# dat1.net
KiCad netlist of a schematic drawn in EAGLE
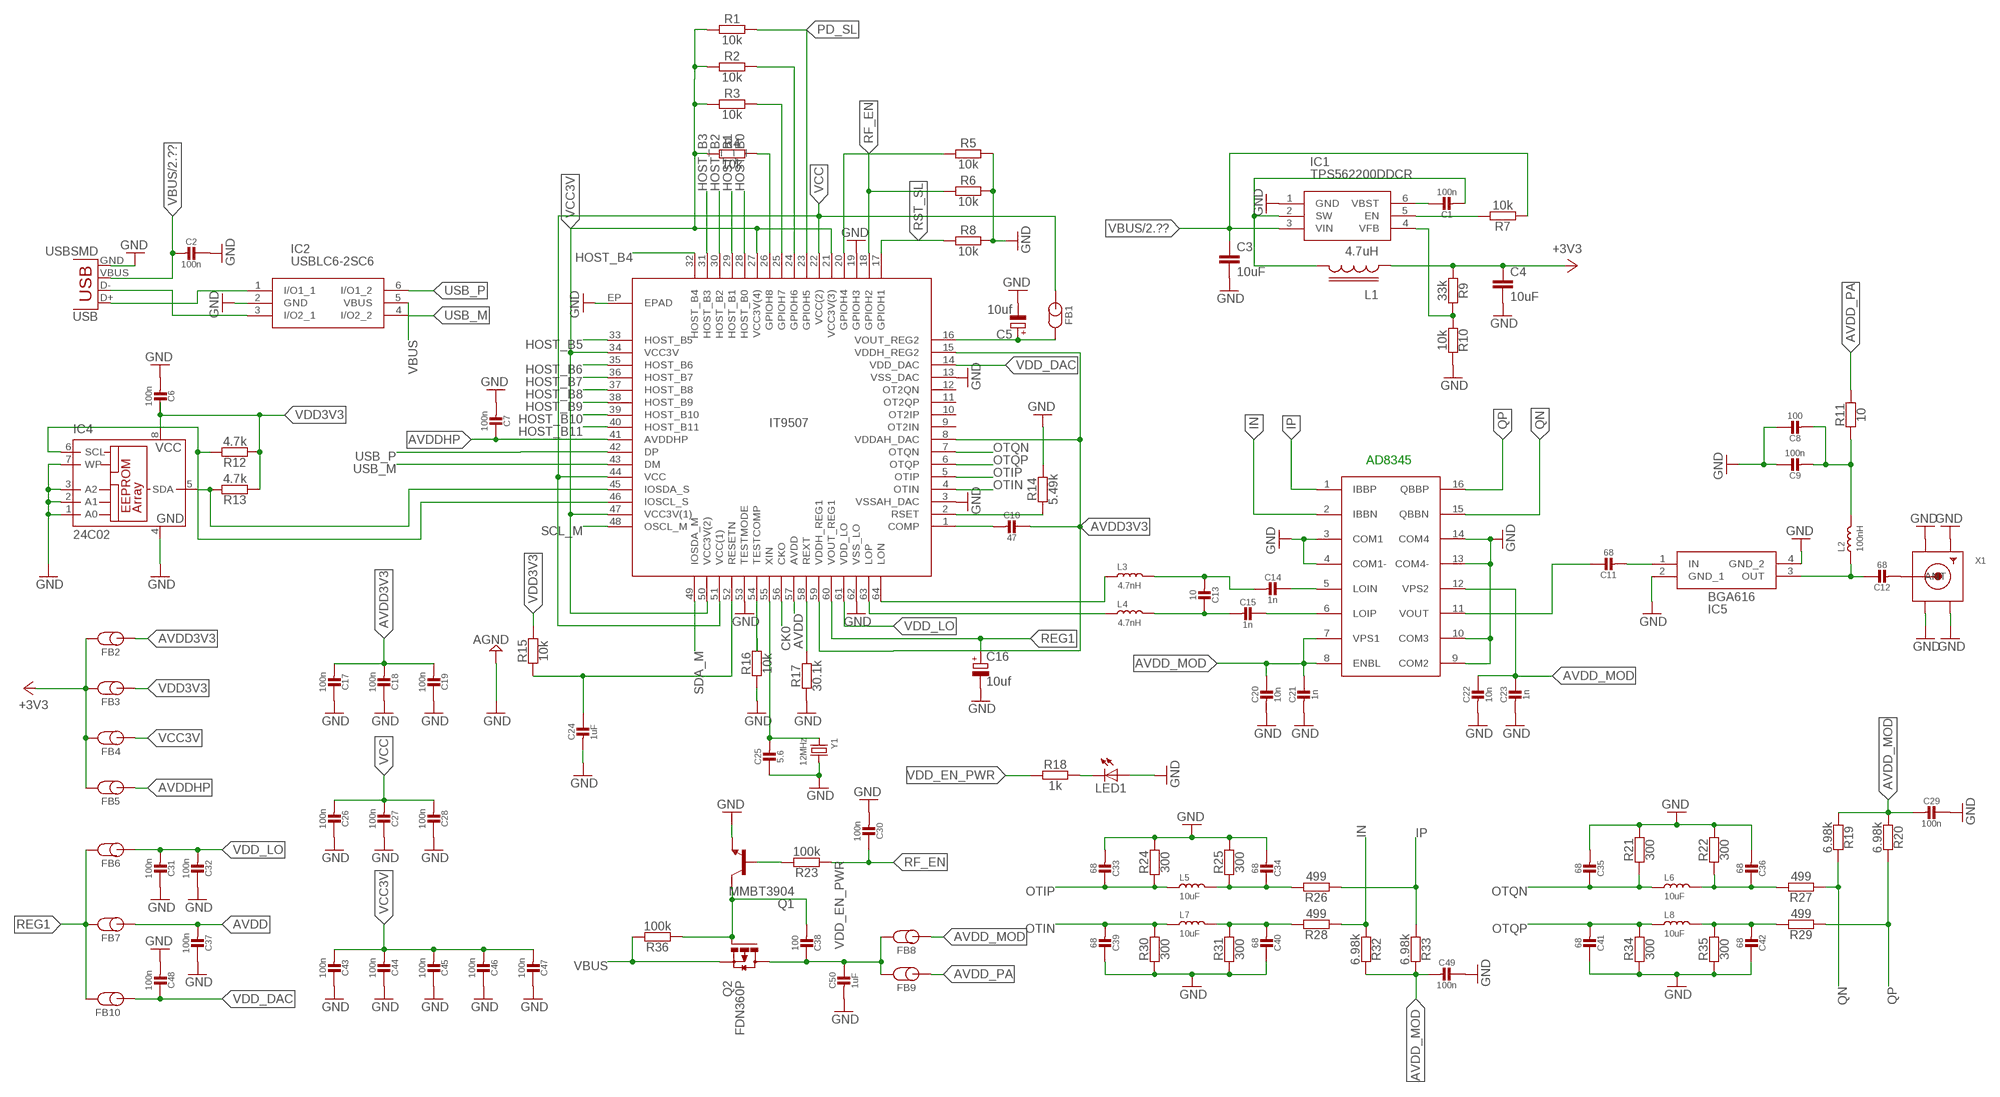
[diagram p0: schematic, sheet 1]
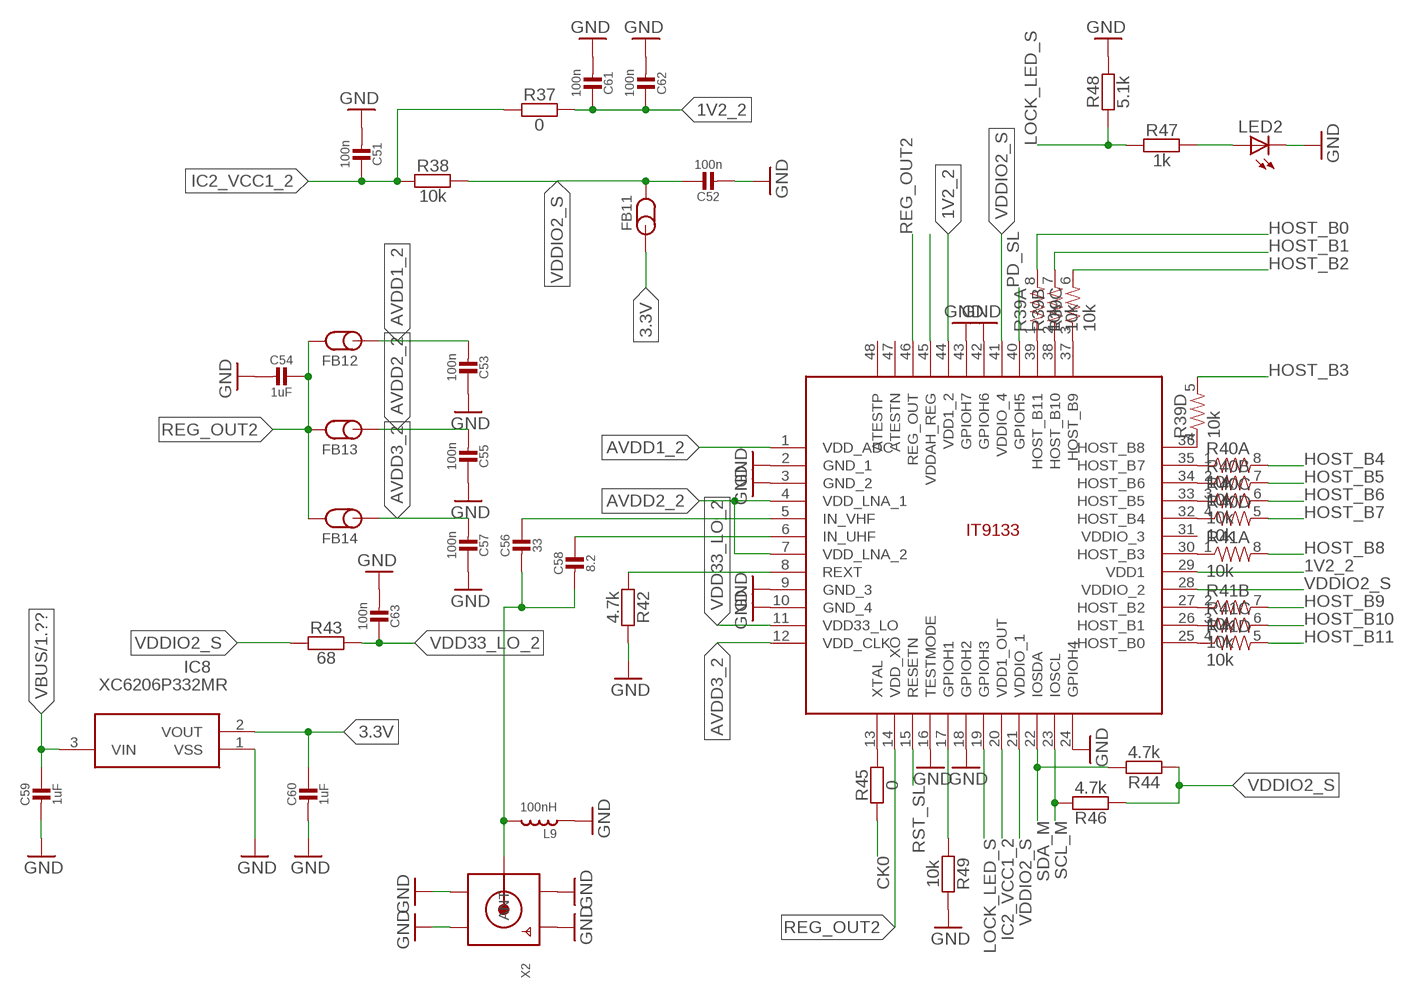
[diagram p1: schematic, sheet 2]

(export (version "E")
  (design (tool "Eeschema 10.0.6"))
  (components
    (comp (ref "C1")
      (value "100n")
      (footprint "eagle-import:_0402")
      (libsource (lib "eagle-import") (part "CAP_CERAMIC_0402"))
    )
    (comp (ref "C2")
      (value "100n")
      (footprint "eagle-import:_0402")
      (libsource (lib "eagle-import") (part "CAP_CERAMIC_0402"))
    )
    (comp (ref "C3")
      (value "10uF")
      (footprint "eagle-import:C0805K")
      (libsource (lib "eagle-import") (part "C-EUC0805K"))
    )
    (comp (ref "C4")
      (value "10uF")
      (footprint "eagle-import:C0805K")
      (libsource (lib "eagle-import") (part "C-EUC0805K"))
    )
    (comp (ref "C5")
      (value "10uf")
      (footprint "eagle-import:SMC_A")
      (libsource (lib "eagle-import") (part "CPOL-EUSMCA"))
    )
    (comp (ref "C6")
      (value "100n")
      (footprint "eagle-import:_0402")
      (libsource (lib "eagle-import") (part "CAP_CERAMIC_0402"))
    )
    (comp (ref "C7")
      (value "100n")
      (footprint "eagle-import:_0402")
      (libsource (lib "eagle-import") (part "CAP_CERAMIC_0402"))
    )
    (comp (ref "C8")
      (value "100")
      (footprint "eagle-import:_0402")
      (libsource (lib "eagle-import") (part "CAP_CERAMIC_0402"))
    )
    (comp (ref "C9")
      (value "100n")
      (footprint "eagle-import:_0402")
      (libsource (lib "eagle-import") (part "CAP_CERAMIC_0402"))
    )
    (comp (ref "C10")
      (value "47")
      (footprint "eagle-import:_0402")
      (libsource (lib "eagle-import") (part "CAP_CERAMIC_0402"))
    )
    (comp (ref "C11")
      (value "68")
      (footprint "eagle-import:_0402")
      (libsource (lib "eagle-import") (part "CAP_CERAMIC_0402"))
    )
    (comp (ref "C12")
      (value "68")
      (footprint "eagle-import:_0402")
      (libsource (lib "eagle-import") (part "CAP_CERAMIC_0402"))
    )
    (comp (ref "C13")
      (value "10")
      (footprint "eagle-import:_0402")
      (libsource (lib "eagle-import") (part "CAP_CERAMIC_0402"))
    )
    (comp (ref "C14")
      (value "1n")
      (footprint "eagle-import:_0402")
      (libsource (lib "eagle-import") (part "CAP_CERAMIC_0402"))
    )
    (comp (ref "C15")
      (value "1n")
      (footprint "eagle-import:_0402")
      (libsource (lib "eagle-import") (part "CAP_CERAMIC_0402"))
    )
    (comp (ref "C16")
      (value "10uf")
      (footprint "eagle-import:SMC_A")
      (libsource (lib "eagle-import") (part "CPOL-EUSMCA"))
    )
    (comp (ref "C17")
      (value "100n")
      (footprint "eagle-import:_0402")
      (libsource (lib "eagle-import") (part "CAP_CERAMIC_0402"))
    )
    (comp (ref "C18")
      (value "100n")
      (footprint "eagle-import:_0402")
      (libsource (lib "eagle-import") (part "CAP_CERAMIC_0402"))
    )
    (comp (ref "C19")
      (value "100n")
      (footprint "eagle-import:_0402")
      (libsource (lib "eagle-import") (part "CAP_CERAMIC_0402"))
    )
    (comp (ref "C20")
      (value "10n")
      (footprint "eagle-import:_0402")
      (libsource (lib "eagle-import") (part "CAP_CERAMIC_0402"))
    )
    (comp (ref "C21")
      (value "1n")
      (footprint "eagle-import:_0402")
      (libsource (lib "eagle-import") (part "CAP_CERAMIC_0402"))
    )
    (comp (ref "C22")
      (value "10n")
      (footprint "eagle-import:_0402")
      (libsource (lib "eagle-import") (part "CAP_CERAMIC_0402"))
    )
    (comp (ref "C23")
      (value "1n")
      (footprint "eagle-import:_0402")
      (libsource (lib "eagle-import") (part "CAP_CERAMIC_0402"))
    )
    (comp (ref "C24")
      (value "1uF")
      (footprint "eagle-import:_0402")
      (libsource (lib "eagle-import") (part "CAP_CERAMIC_0402"))
    )
    (comp (ref "C25")
      (value "5.6")
      (footprint "eagle-import:_0402")
      (libsource (lib "eagle-import") (part "CAP_CERAMIC_0402"))
    )
    (comp (ref "C26")
      (value "100n")
      (footprint "eagle-import:_0402")
      (libsource (lib "eagle-import") (part "CAP_CERAMIC_0402"))
    )
    (comp (ref "C27")
      (value "100n")
      (footprint "eagle-import:_0402")
      (libsource (lib "eagle-import") (part "CAP_CERAMIC_0402"))
    )
    (comp (ref "C28")
      (value "100n")
      (footprint "eagle-import:_0402")
      (libsource (lib "eagle-import") (part "CAP_CERAMIC_0402"))
    )
    (comp (ref "C29")
      (value "100n")
      (footprint "eagle-import:_0402")
      (libsource (lib "eagle-import") (part "CAP_CERAMIC_0402"))
    )
    (comp (ref "C30")
      (value "100n")
      (footprint "eagle-import:_0402")
      (libsource (lib "eagle-import") (part "CAP_CERAMIC_0402"))
    )
    (comp (ref "C31")
      (value "100n")
      (footprint "eagle-import:_0402")
      (libsource (lib "eagle-import") (part "CAP_CERAMIC_0402"))
    )
    (comp (ref "C32")
      (value "100n")
      (footprint "eagle-import:_0402")
      (libsource (lib "eagle-import") (part "CAP_CERAMIC_0402"))
    )
    (comp (ref "C33")
      (value "68")
      (footprint "eagle-import:_0402")
      (libsource (lib "eagle-import") (part "CAP_CERAMIC_0402"))
    )
    (comp (ref "C34")
      (value "68")
      (footprint "eagle-import:_0402")
      (libsource (lib "eagle-import") (part "CAP_CERAMIC_0402"))
    )
    (comp (ref "C35")
      (value "68")
      (footprint "eagle-import:_0402")
      (libsource (lib "eagle-import") (part "CAP_CERAMIC_0402"))
    )
    (comp (ref "C36")
      (value "68")
      (footprint "eagle-import:_0402")
      (libsource (lib "eagle-import") (part "CAP_CERAMIC_0402"))
    )
    (comp (ref "C37")
      (value "100n")
      (footprint "eagle-import:_0402")
      (libsource (lib "eagle-import") (part "CAP_CERAMIC_0402"))
    )
    (comp (ref "C38")
      (value "100")
      (footprint "eagle-import:_0402")
      (libsource (lib "eagle-import") (part "CAP_CERAMIC_0402"))
    )
    (comp (ref "C39")
      (value "68")
      (footprint "eagle-import:_0402")
      (libsource (lib "eagle-import") (part "CAP_CERAMIC_0402"))
    )
    (comp (ref "C40")
      (value "68")
      (footprint "eagle-import:_0402")
      (libsource (lib "eagle-import") (part "CAP_CERAMIC_0402"))
    )
    (comp (ref "C41")
      (value "68")
      (footprint "eagle-import:_0402")
      (libsource (lib "eagle-import") (part "CAP_CERAMIC_0402"))
    )
    (comp (ref "C42")
      (value "68")
      (footprint "eagle-import:_0402")
      (libsource (lib "eagle-import") (part "CAP_CERAMIC_0402"))
    )
    (comp (ref "C43")
      (value "100n")
      (footprint "eagle-import:_0402")
      (libsource (lib "eagle-import") (part "CAP_CERAMIC_0402"))
    )
    (comp (ref "C44")
      (value "100n")
      (footprint "eagle-import:_0402")
      (libsource (lib "eagle-import") (part "CAP_CERAMIC_0402"))
    )
    (comp (ref "C45")
      (value "100n")
      (footprint "eagle-import:_0402")
      (libsource (lib "eagle-import") (part "CAP_CERAMIC_0402"))
    )
    (comp (ref "C46")
      (value "100n")
      (footprint "eagle-import:_0402")
      (libsource (lib "eagle-import") (part "CAP_CERAMIC_0402"))
    )
    (comp (ref "C47")
      (value "100n")
      (footprint "eagle-import:_0402")
      (libsource (lib "eagle-import") (part "CAP_CERAMIC_0402"))
    )
    (comp (ref "C48")
      (value "100n")
      (footprint "eagle-import:_0402")
      (libsource (lib "eagle-import") (part "CAP_CERAMIC_0402"))
    )
    (comp (ref "C49")
      (value "100n")
      (footprint "eagle-import:_0402")
      (libsource (lib "eagle-import") (part "CAP_CERAMIC_0402"))
    )
    (comp (ref "C50")
      (value "1uF")
      (footprint "eagle-import:_0603")
      (libsource (lib "eagle-import") (part "CAP_CERAMIC_0603"))
    )
    (comp (ref "FB1")
      (value "FB0603")
      (footprint "eagle-import:INDC1608X95N")
      (libsource (lib "eagle-import") (part "FB0603"))
    )
    (comp (ref "FB2")
      (value "FB0603")
      (footprint "eagle-import:INDC1608X95N")
      (libsource (lib "eagle-import") (part "FB0603"))
    )
    (comp (ref "FB3")
      (value "FB0603")
      (footprint "eagle-import:INDC1608X95N")
      (libsource (lib "eagle-import") (part "FB0603"))
    )
    (comp (ref "FB4")
      (value "FB0603")
      (footprint "eagle-import:INDC1608X95N")
      (libsource (lib "eagle-import") (part "FB0603"))
    )
    (comp (ref "FB5")
      (value "FB0603")
      (footprint "eagle-import:INDC1608X95N")
      (libsource (lib "eagle-import") (part "FB0603"))
    )
    (comp (ref "FB6")
      (value "FB0603")
      (footprint "eagle-import:INDC1608X95N")
      (libsource (lib "eagle-import") (part "FB0603"))
    )
    (comp (ref "FB7")
      (value "FB0603")
      (footprint "eagle-import:INDC1608X95N")
      (libsource (lib "eagle-import") (part "FB0603"))
    )
    (comp (ref "FB8")
      (value "FB0603")
      (footprint "eagle-import:INDC1608X95N")
      (libsource (lib "eagle-import") (part "FB0603"))
    )
    (comp (ref "FB9")
      (value "FB0603")
      (footprint "eagle-import:INDC1608X95N")
      (libsource (lib "eagle-import") (part "FB0603"))
    )
    (comp (ref "FB10")
      (value "FB0603")
      (footprint "eagle-import:INDC1608X95N")
      (libsource (lib "eagle-import") (part "FB0603"))
    )
    (comp (ref "IC1")
      (value "TPS562200DDCR")
      (footprint "eagle-import:SOT95P280X110-6N")
      (fields (field (name "MOUSER_PART_NUMBER") "595-TPS562200DDCR"))
      (libsource (lib "eagle-import") (part "TPS562200DDCR"))
    )
    (comp (ref "IC2")
      (value "USBLC6-2SC6")
      (footprint "eagle-import:SOT95P280X145-6N")
      (fields (field (name "MOUSER_PART_NUMBER") "511-USBLC6-2SC6"))
      (libsource (lib "eagle-import") (part "USBLC6-2SC6"))
    )
    (comp (ref "IC3")
      (value "CRYSTALVIDEO_IT9518")
      (footprint "eagle-import:CRYSTALVIDEO_QFN64P40_IT9518")
      (libsource (lib "eagle-import") (part "CRYSTALVIDEO_IT9518"))
    )
    (comp (ref "IC4")
      (value "24C02")
      (footprint "eagle-import:SO-08")
      (fields (field (name "MPN") "AT24C01BN-SH-B"))
      (libsource (lib "eagle-import") (part "24CSN01A"))
    )
    (comp (ref "IC5")
      (value "BGA616")
      (footprint "eagle-import:BGA616")
      (libsource (lib "eagle-import") (part "BGA616"))
    )
    (comp (ref "IC6")
      (value "AD8346")
      (footprint "eagle-import:QSOP16")
      (libsource (lib "eagle-import") (part "AD8346"))
    )
    (comp (ref "L1")
      (value "4.7uH")
      (footprint "eagle-import:L_3X3")
      (libsource (lib "eagle-import") (part "L3X3"))
    )
    (comp (ref "L2")
      (value "100nH")
      (footprint "eagle-import:L0603@1")
      (libsource (lib "eagle-import") (part "INDUCTOR/FERRITE-BEAD-0603"))
    )
    (comp (ref "L3")
      (value "4.7nH")
      (footprint "eagle-import:L0603@1")
      (libsource (lib "eagle-import") (part "INDUCTOR/FERRITE-BEAD-0603"))
    )
    (comp (ref "L4")
      (value "4.7nH")
      (footprint "eagle-import:L0603@1")
      (libsource (lib "eagle-import") (part "INDUCTOR/FERRITE-BEAD-0603"))
    )
    (comp (ref "L5")
      (value "10uF")
      (footprint "eagle-import:L0805@1")
      (libsource (lib "eagle-import") (part "INDUCTOR/FERRITE-BEAD-0805"))
    )
    (comp (ref "L6")
      (value "10uF")
      (footprint "eagle-import:L0805@1")
      (libsource (lib "eagle-import") (part "INDUCTOR/FERRITE-BEAD-0805"))
    )
    (comp (ref "L7")
      (value "10uF")
      (footprint "eagle-import:L0805@1")
      (libsource (lib "eagle-import") (part "INDUCTOR/FERRITE-BEAD-0805"))
    )
    (comp (ref "L8")
      (value "10uF")
      (footprint "eagle-import:L0805@1")
      (libsource (lib "eagle-import") (part "INDUCTOR/FERRITE-BEAD-0805"))
    )
    (comp (ref "LED1")
      (value "POWER")
      (footprint "eagle-import:CHIPLED-0603-TTW")
      (libsource (lib "eagle-import") (part "LEDCHIPLED-0603-TTW"))
    )
    (comp (ref "Q1")
      (value "MMBT3904")
      (footprint "eagle-import:SOT23-BEC")
      (libsource (lib "eagle-import") (part "-NPN-SOT23-BECMMBT3904LT1"))
    )
    (comp (ref "Q2")
      (value "FDN360P")
      (footprint "eagle-import:SUPER-SOT3")
      (libsource (lib "eagle-import") (part "FDN360P"))
    )
    (comp (ref "R1")
      (value "10k")
      (footprint "eagle-import:C0402")
      (libsource (lib "eagle-import") (part "RESISTORS-0402"))
    )
    (comp (ref "R2")
      (value "10k")
      (footprint "eagle-import:C0402")
      (libsource (lib "eagle-import") (part "RESISTORS-0402"))
    )
    (comp (ref "R3")
      (value "10k")
      (footprint "eagle-import:C0402")
      (libsource (lib "eagle-import") (part "RESISTORS-0402"))
    )
    (comp (ref "R4")
      (value "10k")
      (footprint "eagle-import:C0402")
      (libsource (lib "eagle-import") (part "RESISTORS-0402"))
    )
    (comp (ref "R5")
      (value "10k")
      (footprint "eagle-import:C0402")
      (libsource (lib "eagle-import") (part "RESISTORS-0402"))
    )
    (comp (ref "R6")
      (value "10k")
      (footprint "eagle-import:C0402")
      (libsource (lib "eagle-import") (part "RESISTORS-0402"))
    )
    (comp (ref "R7")
      (value "10k")
      (footprint "eagle-import:C0402")
      (libsource (lib "eagle-import") (part "RESISTORS-0402"))
    )
    (comp (ref "R8")
      (value "10k")
      (footprint "eagle-import:C0402")
      (libsource (lib "eagle-import") (part "RESISTORS-0402"))
    )
    (comp (ref "R9")
      (value "33k")
      (footprint "eagle-import:C0402")
      (libsource (lib "eagle-import") (part "RESISTORS-0402"))
    )
    (comp (ref "R10")
      (value "10k")
      (footprint "eagle-import:C0402")
      (libsource (lib "eagle-import") (part "RESISTORS-0402"))
    )
    (comp (ref "R11")
      (value "10")
      (footprint "eagle-import:C0603")
      (libsource (lib "eagle-import") (part "RESISTORS-0603"))
    )
    (comp (ref "R12")
      (value "4.7k")
      (footprint "eagle-import:C0402")
      (libsource (lib "eagle-import") (part "RESISTORS-0402"))
    )
    (comp (ref "R13")
      (value "4.7k")
      (footprint "eagle-import:C0402")
      (libsource (lib "eagle-import") (part "RESISTORS-0402"))
    )
    (comp (ref "R14")
      (value "5.49k")
      (footprint "eagle-import:C0402")
      (libsource (lib "eagle-import") (part "RESISTORS-0402"))
    )
    (comp (ref "R15")
      (value "10k")
      (footprint "eagle-import:C0402")
      (libsource (lib "eagle-import") (part "RESISTORS-0402"))
    )
    (comp (ref "R16")
      (value "10k")
      (footprint "eagle-import:C0402")
      (libsource (lib "eagle-import") (part "RESISTORS-0402"))
    )
    (comp (ref "R17")
      (value "30.1k")
      (footprint "eagle-import:C0402")
      (libsource (lib "eagle-import") (part "RESISTORS-0402"))
    )
    (comp (ref "R18")
      (value "1k")
      (footprint "eagle-import:C0402")
      (libsource (lib "eagle-import") (part "RESISTORS-0402"))
    )
    (comp (ref "R19")
      (value "6.98k")
      (footprint "eagle-import:C0402")
      (libsource (lib "eagle-import") (part "RESISTORS-0402"))
    )
    (comp (ref "R20")
      (value "6.98k")
      (footprint "eagle-import:C0402")
      (libsource (lib "eagle-import") (part "RESISTORS-0402"))
    )
    (comp (ref "R21")
      (value "300")
      (footprint "eagle-import:C0402")
      (libsource (lib "eagle-import") (part "RESISTORS-0402"))
    )
    (comp (ref "R22")
      (value "300")
      (footprint "eagle-import:C0402")
      (libsource (lib "eagle-import") (part "RESISTORS-0402"))
    )
    (comp (ref "R23")
      (value "100k")
      (footprint "eagle-import:C0603")
      (libsource (lib "eagle-import") (part "RESISTORS-0603"))
    )
    (comp (ref "R24")
      (value "300")
      (footprint "eagle-import:C0402")
      (libsource (lib "eagle-import") (part "RESISTORS-0402"))
    )
    (comp (ref "R25")
      (value "300")
      (footprint "eagle-import:C0402")
      (libsource (lib "eagle-import") (part "RESISTORS-0402"))
    )
    (comp (ref "R26")
      (value "499")
      (footprint "eagle-import:C0402")
      (libsource (lib "eagle-import") (part "RESISTORS-0402"))
    )
    (comp (ref "R27")
      (value "499")
      (footprint "eagle-import:C0402")
      (libsource (lib "eagle-import") (part "RESISTORS-0402"))
    )
    (comp (ref "R28")
      (value "499")
      (footprint "eagle-import:C0402")
      (libsource (lib "eagle-import") (part "RESISTORS-0402"))
    )
    (comp (ref "R29")
      (value "499")
      (footprint "eagle-import:C0402")
      (libsource (lib "eagle-import") (part "RESISTORS-0402"))
    )
    (comp (ref "R30")
      (value "300")
      (footprint "eagle-import:C0402")
      (libsource (lib "eagle-import") (part "RESISTORS-0402"))
    )
    (comp (ref "R31")
      (value "300")
      (footprint "eagle-import:C0402")
      (libsource (lib "eagle-import") (part "RESISTORS-0402"))
    )
    (comp (ref "R32")
      (value "6.98k")
      (footprint "eagle-import:C0402")
      (libsource (lib "eagle-import") (part "RESISTORS-0402"))
    )
    (comp (ref "R33")
      (value "6.98k")
      (footprint "eagle-import:C0402")
      (libsource (lib "eagle-import") (part "RESISTORS-0402"))
    )
    (comp (ref "R34")
      (value "300")
      (footprint "eagle-import:C0402")
      (libsource (lib "eagle-import") (part "RESISTORS-0402"))
    )
    (comp (ref "R35")
      (value "300")
      (footprint "eagle-import:C0402")
      (libsource (lib "eagle-import") (part "RESISTORS-0402"))
    )
    (comp (ref "R36")
      (value "100k")
      (footprint "eagle-import:C0603")
      (libsource (lib "eagle-import") (part "RESISTORS-0603"))
    )
    (comp (ref "USB")
      (value "USBSMD")
      (footprint "eagle-import:USB-MINIB")
      (libsource (lib "eagle-import") (part "USBSMD"))
    )
    (comp (ref "X1")
      (value "MODULATOR_MICROBUILDER_SMACONNECTOR_EDGE_UFL")
      (footprint "eagle-import:MODULATOR_MICROBUILDER_SMA_EDGELAUNCH_UFL")
      (libsource (lib "eagle-import") (part "MODULATOR_MICROBUILDER_SMACONNECTOR_EDGE_UFL"))
    )
    (comp (ref "Y1")
      (value "12MHz")
      (footprint "eagle-import:CRYSTAL_3.2X2.5")
      (libsource (lib "eagle-import") (part "CRYSTAL3.2X2.5"))
    )
    (comp (ref "C51")
      (value "100n")
      (footprint "eagle-import:_0402")
      (libsource (lib "eagle-import") (part "CAP_CERAMIC_0402"))
    )
    (comp (ref "C52")
      (value "100n")
      (footprint "eagle-import:_0402")
      (libsource (lib "eagle-import") (part "CAP_CERAMIC_0402"))
    )
    (comp (ref "C53")
      (value "100n")
      (footprint "eagle-import:_0402")
      (libsource (lib "eagle-import") (part "CAP_CERAMIC_0402"))
    )
    (comp (ref "C54")
      (value "1uF")
      (footprint "eagle-import:_0402")
      (libsource (lib "eagle-import") (part "CAP_CERAMIC_0402"))
    )
    (comp (ref "C55")
      (value "100n")
      (footprint "eagle-import:_0402")
      (libsource (lib "eagle-import") (part "CAP_CERAMIC_0402"))
    )
    (comp (ref "C56")
      (value "33")
      (footprint "eagle-import:_0402")
      (libsource (lib "eagle-import") (part "CAP_CERAMIC_0402"))
    )
    (comp (ref "C57")
      (value "100n")
      (footprint "eagle-import:_0402")
      (libsource (lib "eagle-import") (part "CAP_CERAMIC_0402"))
    )
    (comp (ref "C58")
      (value "8.2")
      (footprint "eagle-import:_0402")
      (libsource (lib "eagle-import") (part "CAP_CERAMIC_0402"))
    )
    (comp (ref "C59")
      (value "1uF")
      (footprint "eagle-import:_0603")
      (libsource (lib "eagle-import") (part "CAP_CERAMIC_0603"))
    )
    (comp (ref "C60")
      (value "1uF")
      (footprint "eagle-import:_0603")
      (libsource (lib "eagle-import") (part "CAP_CERAMIC_0603"))
    )
    (comp (ref "C61")
      (value "100n")
      (footprint "eagle-import:_0402")
      (libsource (lib "eagle-import") (part "CAP_CERAMIC_0402"))
    )
    (comp (ref "C62")
      (value "100n")
      (footprint "eagle-import:_0402")
      (libsource (lib "eagle-import") (part "CAP_CERAMIC_0402"))
    )
    (comp (ref "C63")
      (value "100n")
      (footprint "eagle-import:_0402")
      (libsource (lib "eagle-import") (part "CAP_CERAMIC_0402"))
    )
    (comp (ref "FB11")
      (value "FB0603")
      (footprint "eagle-import:INDC1608X95N")
      (libsource (lib "eagle-import") (part "FB0603"))
    )
    (comp (ref "FB12")
      (value "FB0603")
      (footprint "eagle-import:INDC1608X95N")
      (libsource (lib "eagle-import") (part "FB0603"))
    )
    (comp (ref "FB13")
      (value "FB0603")
      (footprint "eagle-import:INDC1608X95N")
      (libsource (lib "eagle-import") (part "FB0603"))
    )
    (comp (ref "FB14")
      (value "FB0603")
      (footprint "eagle-import:INDC1608X95N")
      (libsource (lib "eagle-import") (part "FB0603"))
    )
    (comp (ref "IC7")
      (value "CRYSTALVIDEO_IT9133")
      (footprint "eagle-import:CRYSTALVIDEO_QFN48P50_IT9133")
      (libsource (lib "eagle-import") (part "CRYSTALVIDEO_IT9133"))
    )
    (comp (ref "IC8")
      (value "XC6206P332MR")
      (footprint "eagle-import:SOT95P280X130-3N")
      (libsource (lib "eagle-import") (part "XC6206P332MR"))
    )
    (comp (ref "L9")
      (value "100nH")
      (footprint "eagle-import:L0603S")
      (libsource (lib "eagle-import") (part "INDUCTOR/FERRITE-BEAD-0603S"))
    )
    (comp (ref "LED2")
      (value "POWER")
      (footprint "eagle-import:CHIPLED-0603-TTW")
      (libsource (lib "eagle-import") (part "LEDCHIPLED-0603-TTW"))
    )
    (comp (ref "R37")
      (value "0")
      (footprint "eagle-import:C0402")
      (libsource (lib "eagle-import") (part "RESISTORS-0402"))
    )
    (comp (ref "R38")
      (value "10k")
      (footprint "eagle-import:C0402")
      (libsource (lib "eagle-import") (part "RESISTORS-0402"))
    )
    (comp (ref "R39")
      (value "10k")
      (footprint "eagle-import:0603-ARV")
      (libsource (lib "eagle-import") (part "RESISTOR-ARRAY0603-ARV"))
    )
    (comp (ref "R40")
      (value "10k")
      (footprint "eagle-import:0603-ARV")
      (libsource (lib "eagle-import") (part "RESISTOR-ARRAY0603-ARV"))
    )
    (comp (ref "R41")
      (value "10k")
      (footprint "eagle-import:0603-ARV")
      (libsource (lib "eagle-import") (part "RESISTOR-ARRAY0603-ARV"))
    )
    (comp (ref "R42")
      (value "4.7k")
      (footprint "eagle-import:C0402")
      (libsource (lib "eagle-import") (part "RESISTORS-0402"))
    )
    (comp (ref "R43")
      (value "68")
      (footprint "eagle-import:C0402")
      (libsource (lib "eagle-import") (part "RESISTORS-0402"))
    )
    (comp (ref "R44")
      (value "4.7k")
      (footprint "eagle-import:C0402")
      (libsource (lib "eagle-import") (part "RESISTORS-0402"))
    )
    (comp (ref "R45")
      (value "0")
      (footprint "eagle-import:C0402")
      (libsource (lib "eagle-import") (part "RESISTORS-0402"))
    )
    (comp (ref "R46")
      (value "4.7k")
      (footprint "eagle-import:C0402")
      (libsource (lib "eagle-import") (part "RESISTORS-0402"))
    )
    (comp (ref "R47")
      (value "1k")
      (footprint "eagle-import:C0402")
      (libsource (lib "eagle-import") (part "RESISTORS-0402"))
    )
    (comp (ref "R48")
      (value "5.1k")
      (footprint "eagle-import:C0402")
      (libsource (lib "eagle-import") (part "RESISTORS-0402"))
    )
    (comp (ref "R49")
      (value "10k")
      (footprint "eagle-import:C0402")
      (libsource (lib "eagle-import") (part "RESISTORS-0402"))
    )
    (comp (ref "X2")
      (value "MODULATOR_MICROBUILDER_SMACONNECTOR_EDGE_UFL")
      (footprint "eagle-import:MODULATOR_MICROBUILDER_SMA_EDGELAUNCH_UFL")
      (libsource (lib "eagle-import") (part "MODULATOR_MICROBUILDER_SMACONNECTOR_EDGE_UFL"))
    )
  )
  (nets
    (net (code "1") (name "+3V3") (class "Default")
      (node (ref "C4") (pin "1") (pinfunction "1_1") (pintype "passive"))
      (node (ref "FB2") (pin "2") (pinfunction "2_2") (pintype "passive"))
      (node (ref "FB3") (pin "2") (pinfunction "2_2") (pintype "passive"))
      (node (ref "FB4") (pin "2") (pinfunction "2_2") (pintype "passive"))
      (node (ref "FB5") (pin "2") (pinfunction "2_2") (pintype "passive"))
      (node (ref "L1") (pin "1") (pinfunction "1_1") (pintype "passive"))
      (node (ref "R9") (pin "1") (pinfunction "1_1") (pintype "passive"))
    )
    (net (code "2") (name "1V2_2") (class "Default")
      (node (ref "C61") (pin "1") (pinfunction "1_1") (pintype "passive"))
      (node (ref "C62") (pin "1") (pinfunction "1_1") (pintype "passive"))
      (node (ref "IC7") (pin "29") (pinfunction "VDD1_29") (pintype "bidirectional"))
      (node (ref "IC7") (pin "44") (pinfunction "VDD1_2_44") (pintype "bidirectional"))
      (node (ref "R37") (pin "2") (pinfunction "2_2") (pintype "passive"))
    )
    (net (code "3") (name "3.3V") (class "Default")
      (node (ref "C60") (pin "1") (pinfunction "1_1") (pintype "passive"))
      (node (ref "FB11") (pin "1") (pinfunction "1_1") (pintype "passive"))
      (node (ref "IC8") (pin "2") (pinfunction "VOUT_2") (pintype "bidirectional"))
    )
    (net (code "4") (name "AGND") (class "Default")
      (node (ref "C16") (pin "-") (pinfunction "-_-") (pintype "passive"))
      (node (ref "C17") (pin "1") (pinfunction "1_1") (pintype "passive"))
      (node (ref "C18") (pin "1") (pinfunction "1_1") (pintype "passive"))
      (node (ref "C19") (pin "1") (pinfunction "1_1") (pintype "passive"))
      (node (ref "C2") (pin "1") (pinfunction "1_1") (pintype "passive"))
      (node (ref "C20") (pin "2") (pinfunction "2_2") (pintype "passive"))
      (node (ref "C21") (pin "2") (pinfunction "2_2") (pintype "passive"))
      (node (ref "C22") (pin "2") (pinfunction "2_2") (pintype "passive"))
      (node (ref "C23") (pin "2") (pinfunction "2_2") (pintype "passive"))
      (node (ref "C24") (pin "2") (pinfunction "2_2") (pintype "passive"))
      (node (ref "C25") (pin "1") (pinfunction "1_1") (pintype "passive"))
      (node (ref "C26") (pin "1") (pinfunction "1_1") (pintype "passive"))
      (node (ref "C27") (pin "1") (pinfunction "1_1") (pintype "passive"))
      (node (ref "C28") (pin "1") (pinfunction "1_1") (pintype "passive"))
      (node (ref "C29") (pin "1") (pinfunction "1_1") (pintype "passive"))
      (node (ref "C3") (pin "2") (pinfunction "2_2") (pintype "passive"))
      (node (ref "C30") (pin "2") (pinfunction "2_2") (pintype "passive"))
      (node (ref "C31") (pin "1") (pinfunction "1_1") (pintype "passive"))
      (node (ref "C32") (pin "1") (pinfunction "1_1") (pintype "passive"))
      (node (ref "C33") (pin "2") (pinfunction "2_2") (pintype "passive"))
      (node (ref "C34") (pin "2") (pinfunction "2_2") (pintype "passive"))
      (node (ref "C35") (pin "2") (pinfunction "2_2") (pintype "passive"))
      (node (ref "C36") (pin "2") (pinfunction "2_2") (pintype "passive"))
      (node (ref "C37") (pin "1") (pinfunction "1_1") (pintype "passive"))
      (node (ref "C39") (pin "1") (pinfunction "1_1") (pintype "passive"))
      (node (ref "C4") (pin "2") (pinfunction "2_2") (pintype "passive"))
      (node (ref "C40") (pin "1") (pinfunction "1_1") (pintype "passive"))
      (node (ref "C41") (pin "1") (pinfunction "1_1") (pintype "passive"))
      (node (ref "C42") (pin "1") (pinfunction "1_1") (pintype "passive"))
      (node (ref "C43") (pin "1") (pinfunction "1_1") (pintype "passive"))
      (node (ref "C44") (pin "1") (pinfunction "1_1") (pintype "passive"))
      (node (ref "C45") (pin "1") (pinfunction "1_1") (pintype "passive"))
      (node (ref "C46") (pin "1") (pinfunction "1_1") (pintype "passive"))
      (node (ref "C47") (pin "1") (pinfunction "1_1") (pintype "passive"))
      (node (ref "C48") (pin "2") (pinfunction "2_2") (pintype "passive"))
      (node (ref "C49") (pin "1") (pinfunction "1_1") (pintype "passive"))
      (node (ref "C5") (pin "-") (pinfunction "-_-") (pintype "passive"))
      (node (ref "C50") (pin "2") (pinfunction "2_2") (pintype "passive"))
      (node (ref "C51") (pin "2") (pinfunction "2_2") (pintype "passive"))
      (node (ref "C52") (pin "2") (pinfunction "2_2") (pintype "passive"))
      (node (ref "C53") (pin "1") (pinfunction "1_1") (pintype "passive"))
      (node (ref "C54") (pin "2") (pinfunction "2_2") (pintype "passive"))
      (node (ref "C55") (pin "1") (pinfunction "1_1") (pintype "passive"))
      (node (ref "C57") (pin "1") (pinfunction "1_1") (pintype "passive"))
      (node (ref "C59") (pin "2") (pinfunction "2_2") (pintype "passive"))
      (node (ref "C6") (pin "2") (pinfunction "2_2") (pintype "passive"))
      (node (ref "C60") (pin "2") (pinfunction "2_2") (pintype "passive"))
      (node (ref "C61") (pin "2") (pinfunction "2_2") (pintype "passive"))
      (node (ref "C62") (pin "2") (pinfunction "2_2") (pintype "passive"))
      (node (ref "C63") (pin "2") (pinfunction "2_2") (pintype "passive"))
      (node (ref "C7") (pin "2") (pinfunction "2_2") (pintype "passive"))
      (node (ref "C8") (pin "1") (pinfunction "1_1") (pintype "passive"))
      (node (ref "C9") (pin "1") (pinfunction "1_1") (pintype "passive"))
      (node (ref "IC1") (pin "1") (pinfunction "GND_1") (pintype "power_in"))
      (node (ref "IC2") (pin "2") (pinfunction "GND_2") (pintype "bidirectional"))
      (node (ref "IC3") (pin "13") (pinfunction "VSS_DAC_13") (pintype "bidirectional"))
      (node (ref "IC3") (pin "19") (pinfunction "GPIOH3_19") (pintype "bidirectional"))
      (node (ref "IC3") (pin "3") (pinfunction "VSSAH_DAC_3") (pintype "bidirectional"))
      (node (ref "IC3") (pin "53") (pinfunction "TESTMODE_53") (pintype "bidirectional"))
      (node (ref "IC3") (pin "62") (pinfunction "VSS_LO_62") (pintype "bidirectional"))
      (node (ref "IC3") (pin "EP") (pinfunction "EPAD_EP") (pintype "bidirectional"))
      (node (ref "IC4") (pin "1") (pinfunction "A0_1") (pintype "input"))
      (node (ref "IC4") (pin "2") (pinfunction "A1_2") (pintype "input"))
      (node (ref "IC4") (pin "3") (pinfunction "A2_3") (pintype "input"))
      (node (ref "IC4") (pin "4") (pinfunction "GND_4") (pintype "power_in"))
      (node (ref "IC4") (pin "7") (pinfunction "WP_7") (pintype "input"))
      (node (ref "IC5") (pin "2") (pinfunction "GND_1_2") (pintype "bidirectional"))
      (node (ref "IC5") (pin "4") (pinfunction "GND_2_4") (pintype "bidirectional"))
      (node (ref "IC6") (pin "10") (pinfunction "COM3_10") (pintype "bidirectional"))
      (node (ref "IC6") (pin "13") (pinfunction "COM4-_13") (pintype "bidirectional"))
      (node (ref "IC6") (pin "14") (pinfunction "COM4_14") (pintype "bidirectional"))
      (node (ref "IC6") (pin "3") (pinfunction "COM1_3") (pintype "bidirectional"))
      (node (ref "IC6") (pin "4") (pinfunction "COM1-_4") (pintype "bidirectional"))
      (node (ref "IC6") (pin "9") (pinfunction "COM2_9") (pintype "bidirectional"))
      (node (ref "IC7") (pin "10") (pinfunction "GND_4_10") (pintype "bidirectional"))
      (node (ref "IC7") (pin "16") (pinfunction "TESTMODE_16") (pintype "bidirectional"))
      (node (ref "IC7") (pin "18") (pinfunction "GPIOH2_18") (pintype "bidirectional"))
      (node (ref "IC7") (pin "2") (pinfunction "GND_1_2") (pintype "bidirectional"))
      (node (ref "IC7") (pin "24") (pinfunction "GPIOH4_24") (pintype "bidirectional"))
      (node (ref "IC7") (pin "3") (pinfunction "GND_2_3") (pintype "bidirectional"))
      (node (ref "IC7") (pin "42") (pinfunction "GPIOH6_42") (pintype "bidirectional"))
      (node (ref "IC7") (pin "43") (pinfunction "GPIOH7_43") (pintype "bidirectional"))
      (node (ref "IC7") (pin "9") (pinfunction "GND_3_9") (pintype "bidirectional"))
      (node (ref "IC8") (pin "1") (pinfunction "VSS_1") (pintype "bidirectional"))
      (node (ref "L9") (pin "1") (pinfunction "1_1") (pintype "passive"))
      (node (ref "LED1") (pin "A@1") (pinfunction "A_A@1") (pintype "passive"))
      (node (ref "LED2") (pin "C@1") (pinfunction "C_C@1") (pintype "passive"))
      (node (ref "Q1") (pin "E") (pinfunction "E_E") (pintype "passive"))
      (node (ref "R10") (pin "2") (pinfunction "2_2") (pintype "passive"))
      (node (ref "R14") (pin "2") (pinfunction "2_2") (pintype "passive"))
      (node (ref "R16") (pin "1") (pinfunction "1_1") (pintype "passive"))
      (node (ref "R17") (pin "1") (pinfunction "1_1") (pintype "passive"))
      (node (ref "R21") (pin "2") (pinfunction "2_2") (pintype "passive"))
      (node (ref "R22") (pin "2") (pinfunction "2_2") (pintype "passive"))
      (node (ref "R24") (pin "2") (pinfunction "2_2") (pintype "passive"))
      (node (ref "R25") (pin "2") (pinfunction "2_2") (pintype "passive"))
      (node (ref "R30") (pin "1") (pinfunction "1_1") (pintype "passive"))
      (node (ref "R31") (pin "1") (pinfunction "1_1") (pintype "passive"))
      (node (ref "R34") (pin "1") (pinfunction "1_1") (pintype "passive"))
      (node (ref "R35") (pin "1") (pinfunction "1_1") (pintype "passive"))
      (node (ref "R42") (pin "2") (pinfunction "2_2") (pintype "passive"))
      (node (ref "R48") (pin "2") (pinfunction "2_2") (pintype "passive"))
      (node (ref "R49") (pin "2") (pinfunction "2_2") (pintype "passive"))
      (node (ref "R5") (pin "2") (pinfunction "2_2") (pintype "passive"))
      (node (ref "R6") (pin "2") (pinfunction "2_2") (pintype "passive"))
      (node (ref "R8") (pin "2") (pinfunction "2_2") (pintype "passive"))
      (node (ref "USB") (pin "GND") (pinfunction "GND_GND") (pintype "bidirectional"))
      (node (ref "X1") (pin "GND@1") (pinfunction "GND1_GND@1") (pintype "power_in"))
      (node (ref "X1") (pin "GND@2") (pinfunction "GND2_GND@2") (pintype "power_in"))
      (node (ref "X1") (pin "GND@3") (pinfunction "GND3_GND@3") (pintype "power_in"))
      (node (ref "X1") (pin "GND@4") (pinfunction "GND4_GND@4") (pintype "power_in"))
      (node (ref "X2") (pin "GND@1") (pinfunction "GND1_GND@1") (pintype "power_in"))
      (node (ref "X2") (pin "GND@2") (pinfunction "GND2_GND@2") (pintype "power_in"))
      (node (ref "X2") (pin "GND@3") (pinfunction "GND3_GND@3") (pintype "power_in"))
      (node (ref "X2") (pin "GND@4") (pinfunction "GND4_GND@4") (pintype "power_in"))
      (node (ref "Y1") (pin "2") (pinfunction "2_2") (pintype "passive"))
    )
    (net (code "5") (name "AVDD") (class "Default")
      (node (ref "C37") (pin "2") (pinfunction "2_2") (pintype "passive"))
      (node (ref "FB7") (pin "1") (pinfunction "1_1") (pintype "passive"))
      (node (ref "IC3") (pin "57") (pinfunction "AVDD_57") (pintype "bidirectional"))
    )
    (net (code "6") (name "AVDD1_2") (class "Default")
      (node (ref "C53") (pin "2") (pinfunction "2_2") (pintype "passive"))
      (node (ref "FB12") (pin "1") (pinfunction "1_1") (pintype "passive"))
      (node (ref "IC7") (pin "1") (pinfunction "VDD_ADC_1") (pintype "bidirectional"))
    )
    (net (code "7") (name "AVDD2_2") (class "Default")
      (node (ref "C55") (pin "2") (pinfunction "2_2") (pintype "passive"))
      (node (ref "FB13") (pin "1") (pinfunction "1_1") (pintype "passive"))
      (node (ref "IC7") (pin "4") (pinfunction "VDD_LNA_1_4") (pintype "bidirectional"))
      (node (ref "IC7") (pin "7") (pinfunction "VDD_LNA_2_7") (pintype "bidirectional"))
    )
    (net (code "8") (name "AVDD3V3") (class "Default")
      (node (ref "C10") (pin "1") (pinfunction "1_1") (pintype "passive"))
      (node (ref "C17") (pin "2") (pinfunction "2_2") (pintype "passive"))
      (node (ref "C18") (pin "2") (pinfunction "2_2") (pintype "passive"))
      (node (ref "C19") (pin "2") (pinfunction "2_2") (pintype "passive"))
      (node (ref "FB2") (pin "1") (pinfunction "1_1") (pintype "passive"))
      (node (ref "IC3") (pin "15") (pinfunction "VDDH_REG2_15") (pintype "bidirectional"))
      (node (ref "IC3") (pin "59") (pinfunction "VDDH_REG1_59") (pintype "bidirectional"))
      (node (ref "IC3") (pin "8") (pinfunction "VDDAH_DAC_8") (pintype "bidirectional"))
    )
    (net (code "9") (name "AVDD3_2") (class "Default")
      (node (ref "C57") (pin "2") (pinfunction "2_2") (pintype "passive"))
      (node (ref "FB14") (pin "1") (pinfunction "1_1") (pintype "passive"))
      (node (ref "IC7") (pin "12") (pinfunction "VDD_CLK_12") (pintype "bidirectional"))
    )
    (net (code "10") (name "AVDDHP") (class "Default")
      (node (ref "C7") (pin "1") (pinfunction "1_1") (pintype "passive"))
      (node (ref "FB5") (pin "1") (pinfunction "1_1") (pintype "passive"))
      (node (ref "IC3") (pin "41") (pinfunction "AVDDHP_41") (pintype "bidirectional"))
    )
    (net (code "11") (name "AVDD_MOD") (class "Default")
      (node (ref "C20") (pin "1") (pinfunction "1_1") (pintype "passive"))
      (node (ref "C21") (pin "1") (pinfunction "1_1") (pintype "passive"))
      (node (ref "C22") (pin "1") (pinfunction "1_1") (pintype "passive"))
      (node (ref "C23") (pin "1") (pinfunction "1_1") (pintype "passive"))
      (node (ref "C29") (pin "2") (pinfunction "2_2") (pintype "passive"))
      (node (ref "C49") (pin "2") (pinfunction "2_2") (pintype "passive"))
      (node (ref "FB8") (pin "1") (pinfunction "1_1") (pintype "passive"))
      (node (ref "IC6") (pin "12") (pinfunction "VPS2_12") (pintype "bidirectional"))
      (node (ref "IC6") (pin "7") (pinfunction "VPS1_7") (pintype "bidirectional"))
      (node (ref "IC6") (pin "8") (pinfunction "ENBL_8") (pintype "bidirectional"))
      (node (ref "R19") (pin "1") (pinfunction "1_1") (pintype "passive"))
      (node (ref "R20") (pin "1") (pinfunction "1_1") (pintype "passive"))
      (node (ref "R32") (pin "2") (pinfunction "2_2") (pintype "passive"))
      (node (ref "R33") (pin "2") (pinfunction "2_2") (pintype "passive"))
    )
    (net (code "12") (name "AVDD_PA") (class "Default")
      (node (ref "FB9") (pin "1") (pinfunction "1_1") (pintype "passive"))
      (node (ref "R11") (pin "2") (pinfunction "2_2") (pintype "passive"))
    )
    (net (code "13") (name "CK0") (class "Default")
      (node (ref "IC3") (pin "56") (pinfunction "CKO_56") (pintype "bidirectional"))
      (node (ref "R45") (pin "1") (pinfunction "1_1") (pintype "passive"))
    )
    (net (code "14") (name "HOST_B0") (class "Default")
      (node (ref "IC3") (pin "28") (pinfunction "HOST_B0_28") (pintype "bidirectional"))
      (node (ref "R39") (pin "8") (pinfunction "2_8") (pintype "passive"))
    )
    (net (code "15") (name "HOST_B1") (class "Default")
      (node (ref "IC3") (pin "29") (pinfunction "HOST_B1_29") (pintype "bidirectional"))
      (node (ref "R39") (pin "7") (pinfunction "2_7") (pintype "passive"))
    )
    (net (code "16") (name "HOST_B2") (class "Default")
      (node (ref "IC3") (pin "30") (pinfunction "HOST_B2_30") (pintype "bidirectional"))
      (node (ref "R39") (pin "6") (pinfunction "2_6") (pintype "passive"))
    )
    (net (code "17") (name "HOST_B3") (class "Default")
      (node (ref "IC3") (pin "31") (pinfunction "HOST_B3_31") (pintype "bidirectional"))
      (node (ref "R39") (pin "5") (pinfunction "2_5") (pintype "passive"))
    )
    (net (code "18") (name "HOST_B4") (class "Default")
      (node (ref "IC3") (pin "32") (pinfunction "HOST_B4_32") (pintype "bidirectional"))
      (node (ref "R40") (pin "8") (pinfunction "2_8") (pintype "passive"))
    )
    (net (code "19") (name "HOST_B5") (class "Default")
      (node (ref "IC3") (pin "33") (pinfunction "HOST_B5_33") (pintype "bidirectional"))
      (node (ref "R40") (pin "7") (pinfunction "2_7") (pintype "passive"))
    )
    (net (code "20") (name "HOST_B6") (class "Default")
      (node (ref "IC3") (pin "35") (pinfunction "HOST_B6_35") (pintype "bidirectional"))
      (node (ref "R40") (pin "6") (pinfunction "2_6") (pintype "passive"))
    )
    (net (code "21") (name "HOST_B7") (class "Default")
      (node (ref "IC3") (pin "36") (pinfunction "HOST_B7_36") (pintype "bidirectional"))
      (node (ref "R40") (pin "5") (pinfunction "2_5") (pintype "passive"))
    )
    (net (code "22") (name "HOST_B8") (class "Default")
      (node (ref "IC3") (pin "37") (pinfunction "HOST_B8_37") (pintype "bidirectional"))
      (node (ref "R41") (pin "8") (pinfunction "2_8") (pintype "passive"))
    )
    (net (code "23") (name "HOST_B9") (class "Default")
      (node (ref "IC3") (pin "38") (pinfunction "HOST_B9_38") (pintype "bidirectional"))
      (node (ref "R41") (pin "7") (pinfunction "2_7") (pintype "passive"))
    )
    (net (code "24") (name "HOST_B10") (class "Default")
      (node (ref "IC3") (pin "39") (pinfunction "HOST_B10_39") (pintype "bidirectional"))
      (node (ref "R41") (pin "6") (pinfunction "2_6") (pintype "passive"))
    )
    (net (code "25") (name "HOST_B11") (class "Default")
      (node (ref "IC3") (pin "40") (pinfunction "HOST_B11_40") (pintype "bidirectional"))
      (node (ref "R41") (pin "5") (pinfunction "2_5") (pintype "passive"))
    )
    (net (code "26") (name "IC2_VCC1_2") (class "Default")
      (node (ref "C51") (pin "1") (pinfunction "1_1") (pintype "passive"))
      (node (ref "IC7") (pin "20") (pinfunction "VDD1_OUT_20") (pintype "bidirectional"))
      (node (ref "R37") (pin "1") (pinfunction "1_1") (pintype "passive"))
      (node (ref "R38") (pin "1") (pinfunction "1_1") (pintype "passive"))
    )
    (net (code "27") (name "IN") (class "Default")
      (node (ref "IC6") (pin "2") (pinfunction "IBBN_2") (pintype "bidirectional"))
      (node (ref "R28") (pin "1") (pinfunction "1_1") (pintype "passive"))
      (node (ref "R32") (pin "1") (pinfunction "1_1") (pintype "passive"))
    )
    (net (code "28") (name "IP") (class "Default")
      (node (ref "IC6") (pin "1") (pinfunction "IBBP_1") (pintype "bidirectional"))
      (node (ref "R26") (pin "1") (pinfunction "1_1") (pintype "passive"))
      (node (ref "R33") (pin "1") (pinfunction "1_1") (pintype "passive"))
    )
    (net (code "29") (name "LOCK_LED_S") (class "Default")
      (node (ref "IC7") (pin "19") (pinfunction "GPIOH3_19") (pintype "bidirectional"))
      (node (ref "R47") (pin "1") (pinfunction "1_1") (pintype "passive"))
      (node (ref "R48") (pin "1") (pinfunction "1_1") (pintype "passive"))
    )
    (net (code "30") (name "Net-(C8-Pad2)") (class "Default")
      (node (ref "C8") (pin "2") (pinfunction "2_2") (pintype "passive"))
      (node (ref "C9") (pin "2") (pinfunction "2_2") (pintype "passive"))
      (node (ref "L2") (pin "2") (pinfunction "2_2") (pintype "passive"))
      (node (ref "R11") (pin "1") (pinfunction "1_1") (pintype "passive"))
    )
    (net (code "31") (name "Net-(C13-Pad1)") (class "Default")
      (node (ref "C13") (pin "1") (pinfunction "1_1") (pintype "passive"))
      (node (ref "C15") (pin "2") (pinfunction "2_2") (pintype "passive"))
      (node (ref "L4") (pin "2") (pinfunction "2_2") (pintype "passive"))
    )
    (net (code "32") (name "Net-(C13-Pad2)") (class "Default")
      (node (ref "C13") (pin "2") (pinfunction "2_2") (pintype "passive"))
      (node (ref "C14") (pin "2") (pinfunction "2_2") (pintype "passive"))
      (node (ref "L3") (pin "2") (pinfunction "2_2") (pintype "passive"))
    )
    (net (code "33") (name "Net-(C34-Pad1)") (class "Default")
      (node (ref "C34") (pin "1") (pinfunction "1_1") (pintype "passive"))
      (node (ref "L5") (pin "2") (pinfunction "2_2") (pintype "passive"))
      (node (ref "R25") (pin "1") (pinfunction "1_1") (pintype "passive"))
      (node (ref "R26") (pin "2") (pinfunction "2_2") (pintype "passive"))
    )
    (net (code "34") (name "Net-(C36-Pad1)") (class "Default")
      (node (ref "C36") (pin "1") (pinfunction "1_1") (pintype "passive"))
      (node (ref "L6") (pin "2") (pinfunction "2_2") (pintype "passive"))
      (node (ref "R22") (pin "1") (pinfunction "1_1") (pintype "passive"))
      (node (ref "R27") (pin "2") (pinfunction "2_2") (pintype "passive"))
    )
    (net (code "35") (name "Net-(C40-Pad2)") (class "Default")
      (node (ref "C40") (pin "2") (pinfunction "2_2") (pintype "passive"))
      (node (ref "L7") (pin "2") (pinfunction "2_2") (pintype "passive"))
      (node (ref "R28") (pin "2") (pinfunction "2_2") (pintype "passive"))
      (node (ref "R31") (pin "2") (pinfunction "2_2") (pintype "passive"))
    )
    (net (code "36") (name "Net-(C42-Pad2)") (class "Default")
      (node (ref "C42") (pin "2") (pinfunction "2_2") (pintype "passive"))
      (node (ref "L8") (pin "2") (pinfunction "2_2") (pintype "passive"))
      (node (ref "R29") (pin "2") (pinfunction "2_2") (pintype "passive"))
      (node (ref "R35") (pin "2") (pinfunction "2_2") (pintype "passive"))
    )
    (net (code "37") (name "Net-(IC1-EN)") (class "Default")
      (node (ref "IC1") (pin "5") (pinfunction "EN_5") (pintype "input"))
      (node (ref "R7") (pin "2") (pinfunction "2_2") (pintype "passive"))
    )
    (net (code "38") (name "Net-(IC1-SW)") (class "Default")
      (node (ref "C1") (pin "2") (pinfunction "2_2") (pintype "passive"))
      (node (ref "IC1") (pin "2") (pinfunction "SW_2") (pintype "output"))
      (node (ref "L1") (pin "2") (pinfunction "2_2") (pintype "passive"))
    )
    (net (code "39") (name "Net-(IC1-VBST)") (class "Default")
      (node (ref "C1") (pin "1") (pinfunction "1_1") (pintype "passive"))
      (node (ref "IC1") (pin "6") (pinfunction "VBST_6") (pintype "output"))
    )
    (net (code "40") (name "Net-(IC1-VFB)") (class "Default")
      (node (ref "IC1") (pin "4") (pinfunction "VFB_4") (pintype "output"))
      (node (ref "R10") (pin "1") (pinfunction "1_1") (pintype "passive"))
      (node (ref "R9") (pin "2") (pinfunction "2_2") (pintype "passive"))
    )
    (net (code "41") (name "Net-(IC2-I{slash}O1_1)") (class "Default")
      (node (ref "IC2") (pin "1") (pinfunction "I/O1_1_1") (pintype "bidirectional"))
      (node (ref "USB") (pin "D+") (pinfunction "D+_D+") (pintype "bidirectional"))
    )
    (net (code "42") (name "Net-(IC2-I{slash}O2_1)") (class "Default")
      (node (ref "IC2") (pin "3") (pinfunction "I/O2_1_3") (pintype "bidirectional"))
      (node (ref "USB") (pin "D-") (pinfunction "D-_D-") (pintype "bidirectional"))
    )
    (net (code "43") (name "Net-(IC3-COMP)") (class "Default")
      (node (ref "C10") (pin "2") (pinfunction "2_2") (pintype "passive"))
      (node (ref "IC3") (pin "1") (pinfunction "COMP_1") (pintype "bidirectional"))
    )
    (net (code "44") (name "Net-(IC3-GPIOH4)") (class "Default")
      (node (ref "IC3") (pin "20") (pinfunction "GPIOH4_20") (pintype "bidirectional"))
      (node (ref "R5") (pin "1") (pinfunction "1_1") (pintype "passive"))
    )
    (net (code "45") (name "Net-(IC3-GPIOH6)") (class "Default")
      (node (ref "IC3") (pin "24") (pinfunction "GPIOH6_24") (pintype "bidirectional"))
      (node (ref "R2") (pin "2") (pinfunction "2_2") (pintype "passive"))
    )
    (net (code "46") (name "Net-(IC3-GPIOH7)") (class "Default")
      (node (ref "IC3") (pin "25") (pinfunction "GPIOH7_25") (pintype "bidirectional"))
      (node (ref "R3") (pin "2") (pinfunction "2_2") (pintype "passive"))
    )
    (net (code "47") (name "Net-(IC3-GPIOH8)") (class "Default")
      (node (ref "IC3") (pin "26") (pinfunction "GPIOH8_26") (pintype "bidirectional"))
      (node (ref "R4") (pin "2") (pinfunction "2_2") (pintype "passive"))
    )
    (net (code "48") (name "Net-(IC3-IOSCL_S)") (class "Default")
      (node (ref "IC3") (pin "46") (pinfunction "IOSCL_S_46") (pintype "bidirectional"))
      (node (ref "IC4") (pin "6") (pinfunction "SCL_6") (pintype "input"))
      (node (ref "R12") (pin "2") (pinfunction "2_2") (pintype "passive"))
    )
    (net (code "49") (name "Net-(IC3-IOSDA_S)") (class "Default")
      (node (ref "IC3") (pin "45") (pinfunction "IOSDA_S_45") (pintype "bidirectional"))
      (node (ref "IC4") (pin "5") (pinfunction "SDA_5") (pintype "bidirectional"))
      (node (ref "R13") (pin "2") (pinfunction "2_2") (pintype "passive"))
    )
    (net (code "50") (name "Net-(IC3-LON)") (class "Default")
      (node (ref "IC3") (pin "64") (pinfunction "LON_64") (pintype "bidirectional"))
      (node (ref "L3") (pin "1") (pinfunction "1_1") (pintype "passive"))
    )
    (net (code "51") (name "Net-(IC3-LOP)") (class "Default")
      (node (ref "IC3") (pin "63") (pinfunction "LOP_63") (pintype "bidirectional"))
      (node (ref "L4") (pin "1") (pinfunction "1_1") (pintype "passive"))
    )
    (net (code "52") (name "Net-(IC3-RESETN)") (class "Default")
      (node (ref "C24") (pin "1") (pinfunction "1_1") (pintype "passive"))
      (node (ref "IC3") (pin "52") (pinfunction "RESETN_52") (pintype "bidirectional"))
      (node (ref "R15") (pin "1") (pinfunction "1_1") (pintype "passive"))
    )
    (net (code "53") (name "Net-(IC3-REXT)") (class "Default")
      (node (ref "IC3") (pin "58") (pinfunction "REXT_58") (pintype "bidirectional"))
      (node (ref "R17") (pin "2") (pinfunction "2_2") (pintype "passive"))
    )
    (net (code "54") (name "Net-(IC3-RSET)") (class "Default")
      (node (ref "IC3") (pin "2") (pinfunction "RSET_2") (pintype "bidirectional"))
      (node (ref "R14") (pin "1") (pinfunction "1_1") (pintype "passive"))
    )
    (net (code "55") (name "Net-(IC3-TESTCOMP)") (class "Default")
      (node (ref "IC3") (pin "54") (pinfunction "TESTCOMP_54") (pintype "bidirectional"))
      (node (ref "R16") (pin "2") (pinfunction "2_2") (pintype "passive"))
    )
    (net (code "56") (name "Net-(IC3-VOUT_REG2)") (class "Default")
      (node (ref "C5") (pin "+") (pinfunction "+_+") (pintype "passive"))
      (node (ref "FB1") (pin "2") (pinfunction "2_2") (pintype "passive"))
      (node (ref "IC3") (pin "16") (pinfunction "VOUT_REG2_16") (pintype "bidirectional"))
    )
    (net (code "57") (name "Net-(IC3-XIN)") (class "Default")
      (node (ref "C25") (pin "2") (pinfunction "2_2") (pintype "passive"))
      (node (ref "IC3") (pin "55") (pinfunction "XIN_55") (pintype "bidirectional"))
      (node (ref "Y1") (pin "1") (pinfunction "1_1") (pintype "passive"))
    )
    (net (code "58") (name "Net-(IC5-IN)") (class "Default")
      (node (ref "C11") (pin "2") (pinfunction "2_2") (pintype "passive"))
      (node (ref "IC5") (pin "1") (pinfunction "IN_1") (pintype "bidirectional"))
    )
    (net (code "59") (name "Net-(IC5-OUT)") (class "Default")
      (node (ref "C12") (pin "1") (pinfunction "1_1") (pintype "passive"))
      (node (ref "IC5") (pin "3") (pinfunction "OUT_3") (pintype "bidirectional"))
      (node (ref "L2") (pin "1") (pinfunction "1_1") (pintype "passive"))
    )
    (net (code "60") (name "Net-(IC6-LOIN)") (class "Default")
      (node (ref "C14") (pin "1") (pinfunction "1_1") (pintype "passive"))
      (node (ref "IC6") (pin "5") (pinfunction "LOIN_5") (pintype "bidirectional"))
    )
    (net (code "61") (name "Net-(IC6-LOIP)") (class "Default")
      (node (ref "C15") (pin "1") (pinfunction "1_1") (pintype "passive"))
      (node (ref "IC6") (pin "6") (pinfunction "LOIP_6") (pintype "bidirectional"))
    )
    (net (code "62") (name "Net-(IC6-VOUT)") (class "Default")
      (node (ref "C11") (pin "1") (pinfunction "1_1") (pintype "passive"))
      (node (ref "IC6") (pin "11") (pinfunction "VOUT_11") (pintype "bidirectional"))
    )
    (net (code "63") (name "Net-(IC7-GPIOH1)") (class "Default")
      (node (ref "IC7") (pin "17") (pinfunction "GPIOH1_17") (pintype "bidirectional"))
      (node (ref "R49") (pin "1") (pinfunction "1_1") (pintype "passive"))
    )
    (net (code "64") (name "Net-(IC7-HOST_B0)") (class "Default")
      (node (ref "IC7") (pin "25") (pinfunction "HOST_B0_25") (pintype "bidirectional"))
      (node (ref "R41") (pin "4") (pinfunction "1_4") (pintype "passive"))
    )
    (net (code "65") (name "Net-(IC7-HOST_B1)") (class "Default")
      (node (ref "IC7") (pin "26") (pinfunction "HOST_B1_26") (pintype "bidirectional"))
      (node (ref "R41") (pin "3") (pinfunction "1_3") (pintype "passive"))
    )
    (net (code "66") (name "Net-(IC7-HOST_B2)") (class "Default")
      (node (ref "IC7") (pin "27") (pinfunction "HOST_B2_27") (pintype "bidirectional"))
      (node (ref "R41") (pin "2") (pinfunction "1_2") (pintype "passive"))
    )
    (net (code "67") (name "Net-(IC7-HOST_B3)") (class "Default")
      (node (ref "IC7") (pin "30") (pinfunction "HOST_B3_30") (pintype "bidirectional"))
      (node (ref "R41") (pin "1") (pinfunction "1_1") (pintype "passive"))
    )
    (net (code "68") (name "Net-(IC7-HOST_B4)") (class "Default")
      (node (ref "IC7") (pin "32") (pinfunction "HOST_B4_32") (pintype "bidirectional"))
      (node (ref "R40") (pin "4") (pinfunction "1_4") (pintype "passive"))
    )
    (net (code "69") (name "Net-(IC7-HOST_B5)") (class "Default")
      (node (ref "IC7") (pin "33") (pinfunction "HOST_B5_33") (pintype "bidirectional"))
      (node (ref "R40") (pin "3") (pinfunction "1_3") (pintype "passive"))
    )
    (net (code "70") (name "Net-(IC7-HOST_B6)") (class "Default")
      (node (ref "IC7") (pin "34") (pinfunction "HOST_B6_34") (pintype "bidirectional"))
      (node (ref "R40") (pin "2") (pinfunction "1_2") (pintype "passive"))
    )
    (net (code "71") (name "Net-(IC7-HOST_B7)") (class "Default")
      (node (ref "IC7") (pin "35") (pinfunction "HOST_B7_35") (pintype "bidirectional"))
      (node (ref "R40") (pin "1") (pinfunction "1_1") (pintype "passive"))
    )
    (net (code "72") (name "Net-(IC7-HOST_B8)") (class "Default")
      (node (ref "IC7") (pin "36") (pinfunction "HOST_B8_36") (pintype "bidirectional"))
      (node (ref "R39") (pin "4") (pinfunction "1_4") (pintype "passive"))
    )
    (net (code "73") (name "Net-(IC7-HOST_B9)") (class "Default")
      (node (ref "IC7") (pin "37") (pinfunction "HOST_B9_37") (pintype "bidirectional"))
      (node (ref "R39") (pin "3") (pinfunction "1_3") (pintype "passive"))
    )
    (net (code "74") (name "Net-(IC7-HOST_B10)") (class "Default")
      (node (ref "IC7") (pin "38") (pinfunction "HOST_B10_38") (pintype "bidirectional"))
      (node (ref "R39") (pin "2") (pinfunction "1_2") (pintype "passive"))
    )
    (net (code "75") (name "Net-(IC7-HOST_B11)") (class "Default")
      (node (ref "IC7") (pin "39") (pinfunction "HOST_B11_39") (pintype "bidirectional"))
      (node (ref "R39") (pin "1") (pinfunction "1_1") (pintype "passive"))
    )
    (net (code "76") (name "Net-(IC7-IN_UHF)") (class "Default")
      (node (ref "C58") (pin "1") (pinfunction "1_1") (pintype "passive"))
      (node (ref "IC7") (pin "6") (pinfunction "IN_UHF_6") (pintype "bidirectional"))
    )
    (net (code "77") (name "Net-(IC7-IN_VHF)") (class "Default")
      (node (ref "C56") (pin "1") (pinfunction "1_1") (pintype "passive"))
      (node (ref "IC7") (pin "5") (pinfunction "IN_VHF_5") (pintype "bidirectional"))
    )
    (net (code "78") (name "Net-(IC7-REXT)") (class "Default")
      (node (ref "IC7") (pin "8") (pinfunction "REXT_8") (pintype "bidirectional"))
      (node (ref "R42") (pin "1") (pinfunction "1_1") (pintype "passive"))
    )
    (net (code "79") (name "Net-(IC7-XTAL)") (class "Default")
      (node (ref "IC7") (pin "13") (pinfunction "XTAL_13") (pintype "bidirectional"))
      (node (ref "R45") (pin "2") (pinfunction "2_2") (pintype "passive"))
    )
    (net (code "80") (name "Net-(LED1-C)") (class "Default")
      (node (ref "LED1") (pin "C@1") (pinfunction "C_C@1") (pintype "passive"))
      (node (ref "R18") (pin "2") (pinfunction "2_2") (pintype "passive"))
    )
    (net (code "81") (name "Net-(LED2-A)") (class "Default")
      (node (ref "LED2") (pin "A@1") (pinfunction "A_A@1") (pintype "passive"))
      (node (ref "R47") (pin "2") (pinfunction "2_2") (pintype "passive"))
    )
    (net (code "82") (name "Net-(Q1-PadB)") (class "Default")
      (node (ref "Q1") (pin "B") (pinfunction "B_B") (pintype "passive"))
      (node (ref "R23") (pin "2") (pinfunction "2_2") (pintype "passive"))
    )
    (net (code "83") (name "Net-(Q2-G)") (class "Default")
      (node (ref "C38") (pin "2") (pinfunction "2_2") (pintype "passive"))
      (node (ref "Q1") (pin "C") (pinfunction "C_C") (pintype "passive"))
      (node (ref "Q2") (pin "1") (pinfunction "G_1") (pintype "passive"))
      (node (ref "R36") (pin "1") (pinfunction "1_1") (pintype "passive"))
    )
    (net (code "84") (name "Net-(X1-ANT)") (class "Default")
      (node (ref "C12") (pin "2") (pinfunction "2_2") (pintype "passive"))
      (node (ref "X1") (pin "P") (pinfunction "ANT_P") (pintype "bidirectional"))
    )
    (net (code "85") (name "Net-(X2-ANT)") (class "Default")
      (node (ref "C56") (pin "2") (pinfunction "2_2") (pintype "passive"))
      (node (ref "C58") (pin "2") (pinfunction "2_2") (pintype "passive"))
      (node (ref "L9") (pin "2") (pinfunction "2_2") (pintype "passive"))
      (node (ref "X2") (pin "P") (pinfunction "ANT_P") (pintype "bidirectional"))
    )
    (net (code "86") (name "OTIN") (class "Default")
      (node (ref "C39") (pin "2") (pinfunction "2_2") (pintype "passive"))
      (node (ref "IC3") (pin "4") (pinfunction "OTIN_4") (pintype "bidirectional"))
      (node (ref "L7") (pin "1") (pinfunction "1_1") (pintype "passive"))
      (node (ref "R30") (pin "2") (pinfunction "2_2") (pintype "passive"))
    )
    (net (code "87") (name "OTIP") (class "Default")
      (node (ref "C33") (pin "1") (pinfunction "1_1") (pintype "passive"))
      (node (ref "IC3") (pin "5") (pinfunction "OTIP_5") (pintype "bidirectional"))
      (node (ref "L5") (pin "1") (pinfunction "1_1") (pintype "passive"))
      (node (ref "R24") (pin "1") (pinfunction "1_1") (pintype "passive"))
    )
    (net (code "88") (name "OTQN") (class "Default")
      (node (ref "C35") (pin "1") (pinfunction "1_1") (pintype "passive"))
      (node (ref "IC3") (pin "7") (pinfunction "OTQN_7") (pintype "bidirectional"))
      (node (ref "L6") (pin "1") (pinfunction "1_1") (pintype "passive"))
      (node (ref "R21") (pin "1") (pinfunction "1_1") (pintype "passive"))
    )
    (net (code "89") (name "OTQP") (class "Default")
      (node (ref "C41") (pin "2") (pinfunction "2_2") (pintype "passive"))
      (node (ref "IC3") (pin "6") (pinfunction "OTQP_6") (pintype "bidirectional"))
      (node (ref "L8") (pin "1") (pinfunction "1_1") (pintype "passive"))
      (node (ref "R34") (pin "2") (pinfunction "2_2") (pintype "passive"))
    )
    (net (code "90") (name "PD_SL") (class "Default")
      (node (ref "IC3") (pin "23") (pinfunction "GPIOH5_23") (pintype "bidirectional"))
      (node (ref "IC7") (pin "40") (pinfunction "GPIOH5_40") (pintype "bidirectional"))
      (node (ref "R1") (pin "2") (pinfunction "2_2") (pintype "passive"))
    )
    (net (code "91") (name "QN") (class "Default")
      (node (ref "IC6") (pin "15") (pinfunction "QBBN_15") (pintype "bidirectional"))
      (node (ref "R19") (pin "2") (pinfunction "2_2") (pintype "passive"))
      (node (ref "R27") (pin "1") (pinfunction "1_1") (pintype "passive"))
    )
    (net (code "92") (name "QP") (class "Default")
      (node (ref "IC6") (pin "16") (pinfunction "QBBP_16") (pintype "bidirectional"))
      (node (ref "R20") (pin "2") (pinfunction "2_2") (pintype "passive"))
      (node (ref "R29") (pin "1") (pinfunction "1_1") (pintype "passive"))
    )
    (net (code "93") (name "REG1") (class "Default")
      (node (ref "C16") (pin "+") (pinfunction "+_+") (pintype "passive"))
      (node (ref "FB10") (pin "2") (pinfunction "2_2") (pintype "passive"))
      (node (ref "FB6") (pin "2") (pinfunction "2_2") (pintype "passive"))
      (node (ref "FB7") (pin "2") (pinfunction "2_2") (pintype "passive"))
      (node (ref "IC3") (pin "60") (pinfunction "VOUT_REG1_60") (pintype "bidirectional"))
    )
    (net (code "94") (name "REG_OUT2") (class "Default")
      (node (ref "C54") (pin "1") (pinfunction "1_1") (pintype "passive"))
      (node (ref "FB12") (pin "2") (pinfunction "2_2") (pintype "passive"))
      (node (ref "FB13") (pin "2") (pinfunction "2_2") (pintype "passive"))
      (node (ref "FB14") (pin "2") (pinfunction "2_2") (pintype "passive"))
      (node (ref "IC7") (pin "14") (pinfunction "VDD_XO_14") (pintype "bidirectional"))
      (node (ref "IC7") (pin "46") (pinfunction "REG_OUT_46") (pintype "bidirectional"))
    )
    (net (code "95") (name "RF_EN") (class "Default")
      (node (ref "C30") (pin "1") (pinfunction "1_1") (pintype "passive"))
      (node (ref "IC3") (pin "18") (pinfunction "GPIOH2_18") (pintype "bidirectional"))
      (node (ref "R23") (pin "1") (pinfunction "1_1") (pintype "passive"))
      (node (ref "R6") (pin "1") (pinfunction "1_1") (pintype "passive"))
    )
    (net (code "96") (name "RST_SL") (class "Default")
      (node (ref "IC3") (pin "17") (pinfunction "GPIOH1_17") (pintype "bidirectional"))
      (node (ref "IC7") (pin "15") (pinfunction "RESETN_15") (pintype "bidirectional"))
      (node (ref "R8") (pin "1") (pinfunction "1_1") (pintype "passive"))
    )
    (net (code "97") (name "SCL_M") (class "Default")
      (node (ref "IC3") (pin "48") (pinfunction "OSCL_M_48") (pintype "bidirectional"))
      (node (ref "IC7") (pin "23") (pinfunction "IOSCL_23") (pintype "bidirectional"))
      (node (ref "R46") (pin "2") (pinfunction "2_2") (pintype "passive"))
    )
    (net (code "98") (name "SDA_M") (class "Default")
      (node (ref "IC3") (pin "49") (pinfunction "IOSDA_M_49") (pintype "bidirectional"))
      (node (ref "IC7") (pin "22") (pinfunction "IOSDA_22") (pintype "bidirectional"))
      (node (ref "R44") (pin "2") (pinfunction "2_2") (pintype "passive"))
    )
    (net (code "99") (name "USB_M") (class "Default")
      (node (ref "IC2") (pin "4") (pinfunction "I/O2_2_4") (pintype "bidirectional"))
      (node (ref "IC3") (pin "43") (pinfunction "DM_43") (pintype "bidirectional"))
    )
    (net (code "100") (name "USB_P") (class "Default")
      (node (ref "IC2") (pin "6") (pinfunction "I/O1_2_6") (pintype "bidirectional"))
      (node (ref "IC3") (pin "42") (pinfunction "DP_42") (pintype "bidirectional"))
    )
    (net (code "101") (name "VBUS") (class "Default")
      (node (ref "C2") (pin "2") (pinfunction "2_2") (pintype "passive"))
      (node (ref "C3") (pin "1") (pinfunction "1_1") (pintype "passive"))
      (node (ref "C59") (pin "1") (pinfunction "1_1") (pintype "passive"))
      (node (ref "IC1") (pin "3") (pinfunction "VIN_3") (pintype "input"))
      (node (ref "IC2") (pin "5") (pinfunction "VBUS_5") (pintype "bidirectional"))
      (node (ref "IC8") (pin "3") (pinfunction "VIN_3") (pintype "bidirectional"))
      (node (ref "Q2") (pin "2") (pinfunction "S_2") (pintype "passive"))
      (node (ref "R36") (pin "2") (pinfunction "2_2") (pintype "passive"))
      (node (ref "R7") (pin "1") (pinfunction "1_1") (pintype "passive"))
      (node (ref "USB") (pin "VBUS") (pinfunction "VBUS_VBUS") (pintype "bidirectional"))
    )
    (net (code "102") (name "VCC") (class "Default")
      (node (ref "C26") (pin "2") (pinfunction "2_2") (pintype "passive"))
      (node (ref "C27") (pin "2") (pinfunction "2_2") (pintype "passive"))
      (node (ref "C28") (pin "2") (pinfunction "2_2") (pintype "passive"))
      (node (ref "FB1") (pin "1") (pinfunction "1_1") (pintype "passive"))
      (node (ref "IC3") (pin "22") (pinfunction "VCC(2)_22") (pintype "bidirectional"))
      (node (ref "IC3") (pin "44") (pinfunction "VCC_44") (pintype "bidirectional"))
      (node (ref "IC3") (pin "51") (pinfunction "VCC(1)_51") (pintype "bidirectional"))
    )
    (net (code "103") (name "VCC3V") (class "Default")
      (node (ref "C43") (pin "2") (pinfunction "2_2") (pintype "passive"))
      (node (ref "C44") (pin "2") (pinfunction "2_2") (pintype "passive"))
      (node (ref "C45") (pin "2") (pinfunction "2_2") (pintype "passive"))
      (node (ref "C46") (pin "2") (pinfunction "2_2") (pintype "passive"))
      (node (ref "C47") (pin "2") (pinfunction "2_2") (pintype "passive"))
      (node (ref "FB4") (pin "1") (pinfunction "1_1") (pintype "passive"))
      (node (ref "IC3") (pin "21") (pinfunction "VCC3V(3)_21") (pintype "bidirectional"))
      (node (ref "IC3") (pin "27") (pinfunction "VCC3V(4)_27") (pintype "bidirectional"))
      (node (ref "IC3") (pin "34") (pinfunction "VCC3V_34") (pintype "bidirectional"))
      (node (ref "IC3") (pin "47") (pinfunction "VCC3V(1)_47") (pintype "bidirectional"))
      (node (ref "IC3") (pin "50") (pinfunction "VCC3V(2)_50") (pintype "bidirectional"))
      (node (ref "R1") (pin "1") (pinfunction "1_1") (pintype "passive"))
      (node (ref "R2") (pin "1") (pinfunction "1_1") (pintype "passive"))
      (node (ref "R3") (pin "1") (pinfunction "1_1") (pintype "passive"))
      (node (ref "R4") (pin "1") (pinfunction "1_1") (pintype "passive"))
    )
    (net (code "104") (name "VDD3V3") (class "Default")
      (node (ref "C6") (pin "1") (pinfunction "1_1") (pintype "passive"))
      (node (ref "FB3") (pin "1") (pinfunction "1_1") (pintype "passive"))
      (node (ref "IC4") (pin "8") (pinfunction "VCC_8") (pintype "power_in"))
      (node (ref "R12") (pin "1") (pinfunction "1_1") (pintype "passive"))
      (node (ref "R13") (pin "1") (pinfunction "1_1") (pintype "passive"))
      (node (ref "R15") (pin "2") (pinfunction "2_2") (pintype "passive"))
    )
    (net (code "105") (name "VDD33_LO_2") (class "Default")
      (node (ref "C63") (pin "1") (pinfunction "1_1") (pintype "passive"))
      (node (ref "IC7") (pin "11") (pinfunction "VDD33_LO_11") (pintype "bidirectional"))
      (node (ref "R43") (pin "2") (pinfunction "2_2") (pintype "passive"))
    )
    (net (code "106") (name "VDDIO2_S") (class "Default")
      (node (ref "C52") (pin "1") (pinfunction "1_1") (pintype "passive"))
      (node (ref "FB11") (pin "2") (pinfunction "2_2") (pintype "passive"))
      (node (ref "IC7") (pin "21") (pinfunction "VDDIO_1_21") (pintype "bidirectional"))
      (node (ref "IC7") (pin "28") (pinfunction "VDDIO_2_28") (pintype "bidirectional"))
      (node (ref "IC7") (pin "41") (pinfunction "VDDIO_4_41") (pintype "bidirectional"))
      (node (ref "R38") (pin "2") (pinfunction "2_2") (pintype "passive"))
      (node (ref "R43") (pin "1") (pinfunction "1_1") (pintype "passive"))
      (node (ref "R44") (pin "1") (pinfunction "1_1") (pintype "passive"))
      (node (ref "R46") (pin "1") (pinfunction "1_1") (pintype "passive"))
    )
    (net (code "107") (name "VDD_DAC") (class "Default")
      (node (ref "C48") (pin "1") (pinfunction "1_1") (pintype "passive"))
      (node (ref "FB10") (pin "1") (pinfunction "1_1") (pintype "passive"))
      (node (ref "IC3") (pin "14") (pinfunction "VDD_DAC_14") (pintype "bidirectional"))
    )
    (net (code "108") (name "VDD_EN_PWR") (class "Default")
      (node (ref "C38") (pin "1") (pinfunction "1_1") (pintype "passive"))
      (node (ref "C50") (pin "1") (pinfunction "1_1") (pintype "passive"))
      (node (ref "FB8") (pin "2") (pinfunction "2_2") (pintype "passive"))
      (node (ref "FB9") (pin "2") (pinfunction "2_2") (pintype "passive"))
      (node (ref "Q2") (pin "3") (pinfunction "D_3") (pintype "passive"))
      (node (ref "R18") (pin "1") (pinfunction "1_1") (pintype "passive"))
    )
    (net (code "109") (name "VDD_LO") (class "Default")
      (node (ref "C31") (pin "2") (pinfunction "2_2") (pintype "passive"))
      (node (ref "C32") (pin "2") (pinfunction "2_2") (pintype "passive"))
      (node (ref "FB6") (pin "1") (pinfunction "1_1") (pintype "passive"))
      (node (ref "IC3") (pin "61") (pinfunction "VDD_LO_61") (pintype "bidirectional"))
    )
    (net (code "110") (name "unconnected-(IC3-OT2IN-Pad9)") (class "Default")
      (node (ref "IC3") (pin "9") (pinfunction "OT2IN_9") (pintype "bidirectional"))
    )
    (net (code "111") (name "unconnected-(IC3-OT2IP-Pad10)") (class "Default")
      (node (ref "IC3") (pin "10") (pinfunction "OT2IP_10") (pintype "bidirectional"))
    )
    (net (code "112") (name "unconnected-(IC3-OT2QN-Pad12)") (class "Default")
      (node (ref "IC3") (pin "12") (pinfunction "OT2QN_12") (pintype "bidirectional"))
    )
    (net (code "113") (name "unconnected-(IC3-OT2QP-Pad11)") (class "Default")
      (node (ref "IC3") (pin "11") (pinfunction "OT2QP_11") (pintype "bidirectional"))
    )
    (net (code "114") (name "unconnected-(IC7-ATESTN-Pad47)") (class "Default")
      (node (ref "IC7") (pin "47") (pinfunction "ATESTN_47") (pintype "bidirectional"))
    )
    (net (code "115") (name "unconnected-(IC7-ATESTP-Pad48)") (class "Default")
      (node (ref "IC7") (pin "48") (pinfunction "ATESTP_48") (pintype "bidirectional"))
    )
    (net (code "116") (name "unconnected-(IC7-VDDAH_REG-Pad45)") (class "Default")
      (node (ref "IC7") (pin "45") (pinfunction "VDDAH_REG_45") (pintype "bidirectional"))
    )
    (net (code "117") (name "unconnected-(IC7-VDDIO_3-Pad31)") (class "Default")
      (node (ref "IC7") (pin "31") (pinfunction "VDDIO_3_31") (pintype "bidirectional"))
    )
  )
)
